# 08_Power_Supply.net
KiCad netlist of a schematic drawn in Altium Designer
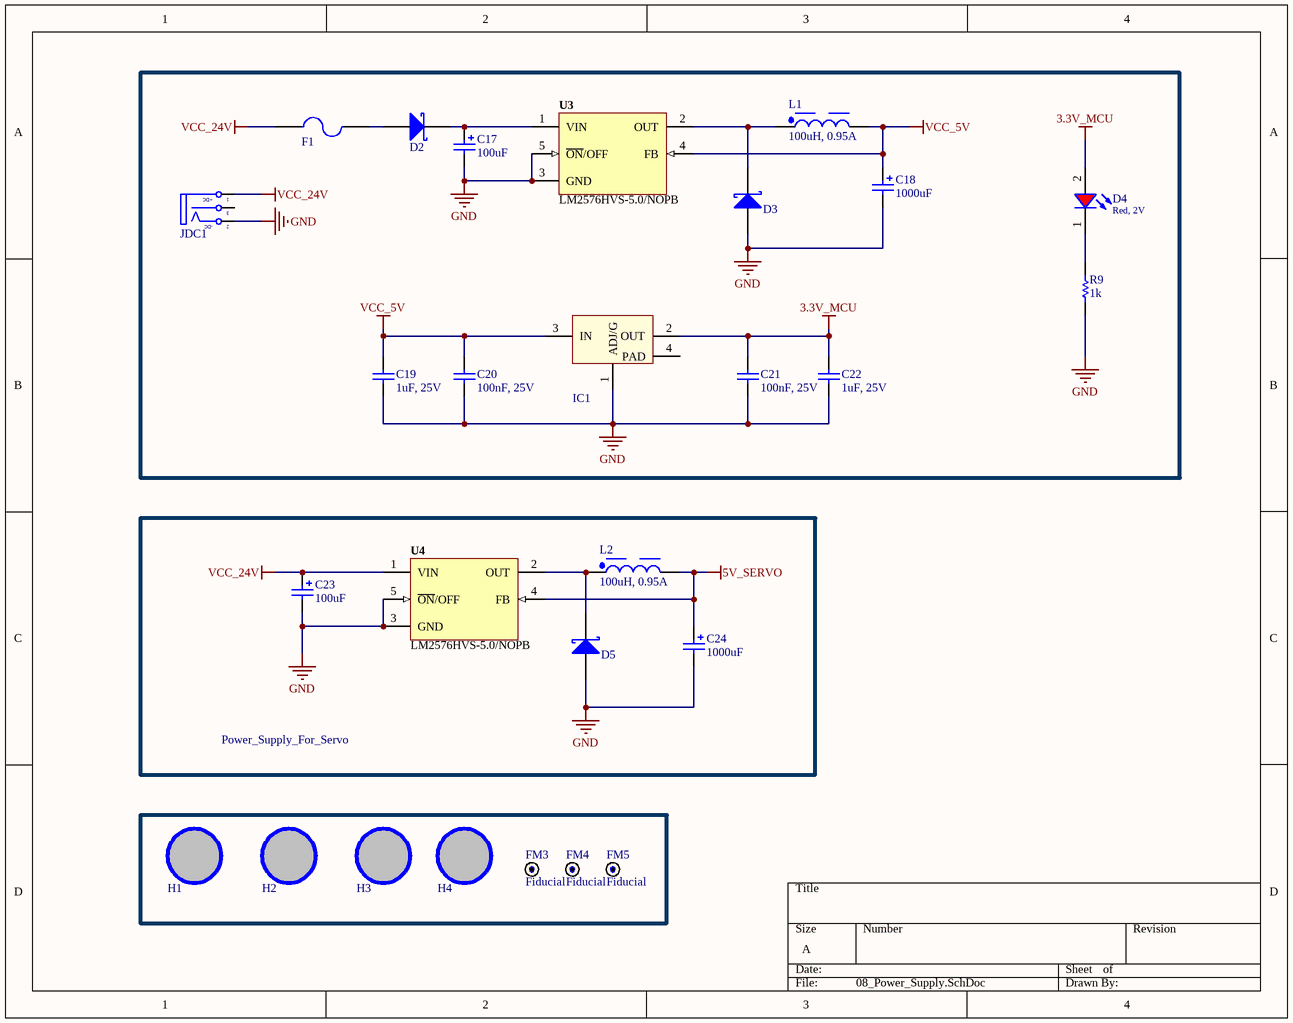
[diagram p0: 08_Power_Supply.SchDoc]

(export (version "E")
  (design (tool "Eeschema 10.0.6"))
  (components
    (comp (ref "C17")
      (value "100uF")
      (footprint "WCAP-ATG8_D6.3H11")
      (description "WCAP-ATG8 Aluminum Electrolytic Capacitor, Radial THT, D6.3xH11mm, 100uF, 25V")
      (fields
        (field (name "MANUFACTURER") "Wurth Elektronik")
        (field (name "MANUFACTURER PART NUMBER") "860010473007")
      )
      (libsource (lib "Altium_WCAP-ATG8 (rev22a)") (part "860010473007"))
    )
    (comp (ref "C18")
      (value "1000uF")
      (footprint "WCAP-ATG8_D10H20")
      (description "WCAP-ATG8 Aluminum Electrolytic Capacitor, Radial THT, D10xH20mm, 1000uF, 25V")
      (fields
        (field (name "MANUFACTURER") "Wurth Elektronik")
        (field (name "MANUFACTURER PART NUMBER") "860010475017")
      )
      (libsource (lib "Altium_WCAP-ATG8 (rev22a)") (part "860010475017"))
    )
    (comp (ref "C19")
      (value "1uF, 25V")
      (footprint "WCAP-CSGP_0603_H=0.8mm_Reflow")
      (description "WCAP-CSGP Multilayer Ceramic Chip Capacitor, General Purpose, size 0603, X5R, 1uF, 25V")
      (fields
        (field (name "MANUFACTURER PART NUMBER") "885012106022")
        (field (name "MANUFACTURER") "Wurth Elektronik")
      )
      (libsource (lib "Altium_WCAP-CSGP (rev20a)") (part "885012106022"))
    )
    (comp (ref "C20")
      (value "100nF, 25V")
      (footprint "WCAP-CSGP_0603_H=0.8mm_Reflow")
      (description "WCAP-CSGP Multilayer Ceramic Chip Capacitor, General Purpose, size 0603, X7R, 100nF, 25V")
      (fields
        (field (name "MANUFACTURER PART NUMBER") "885012206071")
        (field (name "MANUFACTURER") "Wurth Elektronik")
      )
      (libsource (lib "Altium_WCAP-CSGP (rev20a)") (part "885012206071"))
    )
    (comp (ref "C21")
      (value "100nF, 25V")
      (footprint "WCAP-CSGP_0603_H=0.8mm_Reflow")
      (description "WCAP-CSGP Multilayer Ceramic Chip Capacitor, General Purpose, size 0603, X7R, 100nF, 25V")
      (fields
        (field (name "MANUFACTURER PART NUMBER") "885012206071")
        (field (name "MANUFACTURER") "Wurth Elektronik")
      )
      (libsource (lib "Altium_WCAP-CSGP (rev20a)") (part "885012206071"))
    )
    (comp (ref "C22")
      (value "1uF, 25V")
      (footprint "WCAP-CSGP_0603_H=0.8mm_Reflow")
      (description "WCAP-CSGP Multilayer Ceramic Chip Capacitor, General Purpose, size 0603, X5R, 1uF, 25V")
      (fields
        (field (name "MANUFACTURER PART NUMBER") "885012106022")
        (field (name "MANUFACTURER") "Wurth Elektronik")
      )
      (libsource (lib "Altium_WCAP-CSGP (rev20a)") (part "885012106022"))
    )
    (comp (ref "C23")
      (value "100uF")
      (footprint "WCAP-ATG8_D6.3H11")
      (description "WCAP-ATG8 Aluminum Electrolytic Capacitor, Radial THT, D6.3xH11mm, 100uF, 25V")
      (fields
        (field (name "MANUFACTURER") "Wurth Elektronik")
        (field (name "MANUFACTURER PART NUMBER") "860010473007")
      )
      (libsource (lib "Altium_WCAP-ATG8 (rev22a)") (part "860010473007"))
    )
    (comp (ref "C24")
      (value "1000uF")
      (footprint "WCAP-ATG8_D10H20")
      (description "WCAP-ATG8 Aluminum Electrolytic Capacitor, Radial THT, D10xH20mm, 1000uF, 25V")
      (fields
        (field (name "MANUFACTURER") "Wurth Elektronik")
        (field (name "MANUFACTURER PART NUMBER") "860010475017")
      )
      (libsource (lib "Altium_WCAP-ATG8 (rev22a)") (part "860010475017"))
    )
    (comp (ref "D2")
      (value "SS34")
      (footprint "SS34")
      (description "DIODE SCHOTTKY 40V 3A SMC")
      (fields (field (name "MFR") "onsemi") (field (name "PUBLISHER") "Altium Limited"))
      (libsource (lib "PIF_Library") (part "D Schottky"))
    )
    (comp (ref "D3")
      (value "SS34")
      (footprint "SS34")
      (description "DIODE SCHOTTKY 40V 3A SMC")
      (fields (field (name "MFR") "onsemi") (field (name "PUBLISHER") "Altium Limited"))
      (libsource (lib "PIF_Library") (part "D Schottky"))
    )
    (comp (ref "D4")
      (value "Red, 2V")
      (footprint "WL-SMCW_0603_H=0.7mm")
      (description "WL-SMCW SMT Mono-color Chip LED Waterclear, size 0603, Red, 2V, 140deg")
      (fields (field (name "PART NUMBER") "150060RS75000") (field (name "PUBLISHER") "Wurth Elektronik"))
      (libsource (lib "Altium_WL-SMCW (rev20a)") (part "150060RS75000"))
    )
    (comp (ref "D5")
      (value "SS34")
      (footprint "SS34")
      (description "DIODE SCHOTTKY 40V 3A SMC")
      (fields (field (name "MFR") "onsemi") (field (name "PUBLISHER") "Altium Limited"))
      (libsource (lib "PIF_Library") (part "D Schottky"))
    )
    (comp (ref "F1")
      (value "0ZCG0150BF2C")
      (footprint "FUSE SMD")
      (description "Polymeric PTC Resettable Fuse 24V 1.5 A Ih Surface Mount 1812 (4532 Metric), Concave")
      (fields (field (name "MFR") "Bel Fuse Inc."))
      (libsource (lib "PIF_Library") (part "Fuse"))
    )
    (comp (ref "FM3")
      (value "Fiducial")
      (footprint "FUDICIAL_MARKER")
      (libsource (lib "YenDoo") (part "Fiducial"))
    )
    (comp (ref "FM4")
      (value "Fiducial")
      (footprint "FUDICIAL_MARKER")
      (libsource (lib "YenDoo") (part "Fiducial"))
    )
    (comp (ref "FM5")
      (value "Fiducial")
      (footprint "FUDICIAL_MARKER")
      (libsource (lib "YenDoo") (part "Fiducial"))
    )
    (comp (ref "H1")
      (value "Hole")
      (footprint "LO KHOAN 3MM")
      (description "Hole 3mm")
      (libsource (lib "PIF_Library") (part "Hole"))
    )
    (comp (ref "H2")
      (value "Hole")
      (footprint "LO KHOAN 3MM")
      (description "Hole 3mm")
      (libsource (lib "PIF_Library") (part "Hole"))
    )
    (comp (ref "H3")
      (value "Hole")
      (footprint "LO KHOAN 3MM")
      (description "Hole 3mm")
      (libsource (lib "PIF_Library") (part "Hole"))
    )
    (comp (ref "H4")
      (value "Hole")
      (footprint "LO KHOAN 3MM")
      (description "Hole 3mm")
      (libsource (lib "PIF_Library") (part "Hole"))
    )
    (comp (ref "IC1")
      (value "LM1117IMP-3.3/NOPB")
      (footprint "SOT223-4N")
      (description "Linear Voltage Regulator IC Positive Fixed 1 Output 800mA SOT-223")
      (fields (field (name "MFR") "Texas Instruments"))
      (libsource (lib "PIF_Library") (part "LM1117"))
    )
    (comp (ref "JDC1")
      (value "G-014-4")
      (footprint "DC-IN")
      (description "DC POWER JACK, MATES TO 5.5 X 2.")
      (fields (field (name "MFR") "GlobTek, Inc."))
      (libsource (lib "PIF_Library") (part "Jack DC"))
    )
    (comp (ref "L1")
      (value "100uH, 0.95A")
      (footprint "WE-PD2SR_7850")
      (description "WE-PD2SR SMT Power Inductor, size 7850, 100uH, 0.95A, 467mOhm")
      (fields
        (field (name "MANUFACTURER") "Wurth Elektronik")
        (field (name "MANUFACTURER PART NUMBER") "744787101")
      )
      (libsource (lib "WE-PD2SR (rev22a)") (part "744787101"))
    )
    (comp (ref "L2")
      (value "100uH, 0.95A")
      (footprint "WE-PD2SR_7850")
      (description "WE-PD2SR SMT Power Inductor, size 7850, 100uH, 0.95A, 467mOhm")
      (fields
        (field (name "MANUFACTURER") "Wurth Elektronik")
        (field (name "MANUFACTURER PART NUMBER") "744787101")
      )
      (libsource (lib "WE-PD2SR (rev22a)") (part "744787101"))
    )
    (comp (ref "R9")
      (value "1k")
      (footprint "RES-SM-0603")
      (description "RES SMD 1K OHM 5% 1/4W 0603")
      (fields (field (name "MFR") "Rohm Semiconductor") (field (name "TOLERANCE") "±5%"))
      (libsource (lib "PIF_Library") (part "RESISTOR SMD"))
    )
    (comp (ref "U3")
      (value "LM2576HVS-5.0/NOPB")
      (footprint "TO263")
      (description "IC REG BUCK 5V 3A TO263-5")
      (fields (field (name "MFR") "Texas Instruments"))
      (libsource (lib "TechMT.VN_Lib_Project v2") (part "LM2576"))
    )
    (comp (ref "U4")
      (value "LM2576HVS-5.0/NOPB")
      (footprint "TO263")
      (description "IC REG BUCK 5V 3A TO263-5")
      (fields (field (name "MFR") "Texas Instruments"))
      (libsource (lib "TechMT.VN_Lib_Project v2") (part "LM2576"))
    )
  )
  (nets
    (net (code "1") (name "3.3V_MCU") (class "Default")
      (node (ref "C21") (pin "2") (pinfunction "2_2") (pintype "passive"))
      (node (ref "C22") (pin "2") (pinfunction "2_2") (pintype "passive"))
      (node (ref "D4") (pin "2") (pinfunction "A_2") (pintype "passive"))
      (node (ref "IC1") (pin "2") (pinfunction "OUT_2") (pintype "passive"))
    )
    (net (code "2") (name "5V_SERVO") (class "Default")
      (node (ref "C24") (pin "1") (pinfunction "P_1") (pintype "passive"))
      (node (ref "L2") (pin "2") (pinfunction "2_2") (pintype "passive"))
      (node (ref "U4") (pin "4") (pinfunction "FB_4") (pintype "input"))
    )
    (net (code "3") (name "GND") (class "Default")
      (node (ref "C17") (pin "2") (pinfunction "N_2") (pintype "passive"))
      (node (ref "C18") (pin "2") (pinfunction "N_2") (pintype "passive"))
      (node (ref "C19") (pin "2") (pinfunction "2_2") (pintype "passive"))
      (node (ref "C20") (pin "1") (pinfunction "1_1") (pintype "passive"))
      (node (ref "C21") (pin "1") (pinfunction "1_1") (pintype "passive"))
      (node (ref "C22") (pin "1") (pinfunction "1_1") (pintype "passive"))
      (node (ref "C23") (pin "2") (pinfunction "N_2") (pintype "passive"))
      (node (ref "C24") (pin "2") (pinfunction "N_2") (pintype "passive"))
      (node (ref "D3") (pin "1") (pinfunction "A_1") (pintype "passive"))
      (node (ref "D5") (pin "1") (pinfunction "A_1") (pintype "passive"))
      (node (ref "IC1") (pin "1") (pinfunction "ADJ/G_1") (pintype "passive"))
      (node (ref "JDC1") (pin "2") (pinfunction "TN_2") (pintype "passive"))
      (node (ref "R9") (pin "1") (pinfunction "1_1") (pintype "passive"))
      (node (ref "U3") (pin "3") (pinfunction "GND_3") (pintype "power_in"))
      (node (ref "U3") (pin "5") (pinfunction "~{ON}/OFF_5") (pintype "input"))
      (node (ref "U4") (pin "3") (pinfunction "GND_3") (pintype "power_in"))
      (node (ref "U4") (pin "5") (pinfunction "~{ON}/OFF_5") (pintype "input"))
    )
    (net (code "4") (name "Net-(C17-P)") (class "Default")
      (node (ref "C17") (pin "1") (pinfunction "P_1") (pintype "passive"))
      (node (ref "D2") (pin "2") (pinfunction "K_2") (pintype "passive"))
      (node (ref "U3") (pin "1") (pinfunction "VIN_1") (pintype "power_in"))
    )
    (net (code "5") (name "Net-(D2-A)") (class "Default")
      (node (ref "D2") (pin "1") (pinfunction "A_1") (pintype "passive"))
      (node (ref "F1") (pin "2") (pinfunction "2_2") (pintype "passive"))
    )
    (net (code "6") (name "Net-(D3-K)") (class "Default")
      (node (ref "D3") (pin "2") (pinfunction "K_2") (pintype "passive"))
      (node (ref "L1") (pin "1") (pinfunction "1_1") (pintype "passive"))
      (node (ref "U3") (pin "2") (pinfunction "OUT_2") (pintype "power_in"))
    )
    (net (code "7") (name "Net-(D4-K)") (class "Default")
      (node (ref "D4") (pin "1") (pinfunction "K_1") (pintype "passive"))
      (node (ref "R9") (pin "2") (pinfunction "2_2") (pintype "passive"))
    )
    (net (code "8") (name "Net-(D5-K)") (class "Default")
      (node (ref "D5") (pin "2") (pinfunction "K_2") (pintype "passive"))
      (node (ref "L2") (pin "1") (pinfunction "1_1") (pintype "passive"))
      (node (ref "U4") (pin "2") (pinfunction "OUT_2") (pintype "power_in"))
    )
    (net (code "9") (name "VCC_5V") (class "Default")
      (node (ref "C18") (pin "1") (pinfunction "P_1") (pintype "passive"))
      (node (ref "C19") (pin "1") (pinfunction "1_1") (pintype "passive"))
      (node (ref "C20") (pin "2") (pinfunction "2_2") (pintype "passive"))
      (node (ref "IC1") (pin "3") (pinfunction "IN_3") (pintype "passive"))
      (node (ref "L1") (pin "2") (pinfunction "2_2") (pintype "passive"))
      (node (ref "U3") (pin "4") (pinfunction "FB_4") (pintype "input"))
    )
    (net (code "10") (name "VCC_24V") (class "Default")
      (node (ref "C23") (pin "1") (pinfunction "P_1") (pintype "passive"))
      (node (ref "F1") (pin "1") (pinfunction "1_1") (pintype "passive"))
      (node (ref "JDC1") (pin "1") (pinfunction "T_1") (pintype "passive"))
      (node (ref "U4") (pin "1") (pinfunction "VIN_1") (pintype "power_in"))
    )
    (net (code "11") (name "unconnected-(H1-Pad1)") (class "Default")
      (node (ref "H1") (pin "1") (pinfunction "1_1") (pintype "passive"))
    )
    (net (code "12") (name "unconnected-(H2-Pad1)") (class "Default")
      (node (ref "H2") (pin "1") (pinfunction "1_1") (pintype "passive"))
    )
    (net (code "13") (name "unconnected-(H3-Pad1)") (class "Default")
      (node (ref "H3") (pin "1") (pinfunction "1_1") (pintype "passive"))
    )
    (net (code "14") (name "unconnected-(H4-Pad1)") (class "Default")
      (node (ref "H4") (pin "1") (pinfunction "1_1") (pintype "passive"))
    )
    (net (code "15") (name "unconnected-(IC1-PAD-Pad4)") (class "Default")
      (node (ref "IC1") (pin "4") (pinfunction "PAD_4") (pintype "passive"))
    )
    (net (code "16") (name "unconnected-(JDC1-S-Pad3)") (class "Default")
      (node (ref "JDC1") (pin "3") (pinfunction "S_3") (pintype "power_in"))
    )
  )
)
